# Detailed_Block_Diagram.net
KiCad netlist of a schematic drawn in EAGLE
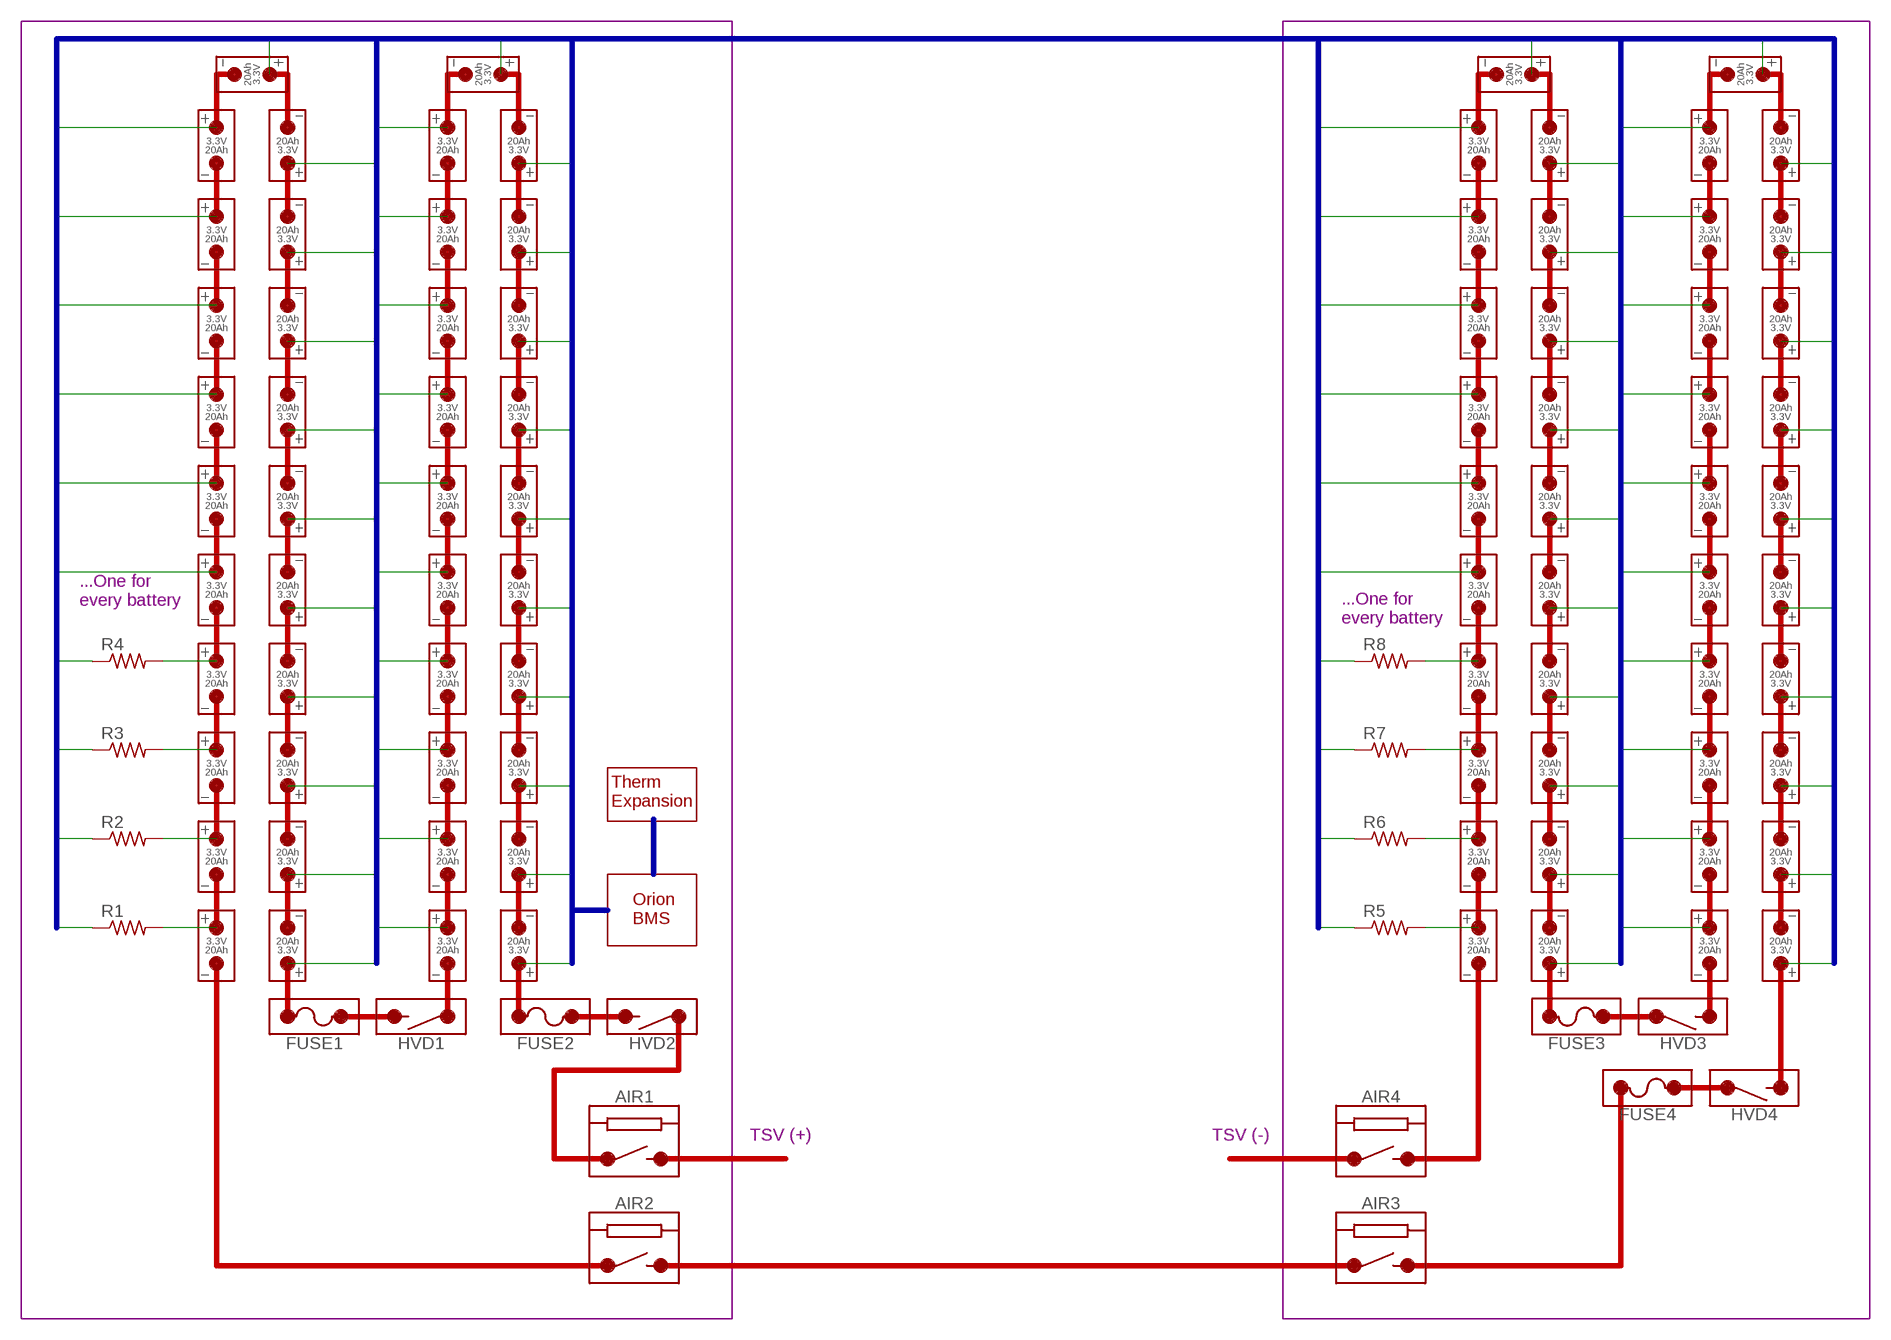
[diagram p0: schematic, sheet 1]

(export (version "E")
  (design (tool "Eeschema 10.0.6"))
  (components
    (comp (ref "AIR1")
      (value "AIR")
      (footprint "eagle-import:AIR")
      (libsource (lib "eagle-import") (part "AIR"))
    )
    (comp (ref "AIR2")
      (value "AIR")
      (footprint "eagle-import:AIR")
      (libsource (lib "eagle-import") (part "AIR"))
    )
    (comp (ref "AIR3")
      (value "AIR")
      (footprint "eagle-import:AIR")
      (libsource (lib "eagle-import") (part "AIR"))
    )
    (comp (ref "AIR4")
      (value "AIR")
      (footprint "eagle-import:AIR")
      (libsource (lib "eagle-import") (part "AIR"))
    )
    (comp (ref "FUSE1")
      (value "FUSE")
      (footprint "eagle-import:FUSE")
      (libsource (lib "eagle-import") (part "FUSE"))
    )
    (comp (ref "FUSE2")
      (value "FUSE")
      (footprint "eagle-import:FUSE")
      (libsource (lib "eagle-import") (part "FUSE"))
    )
    (comp (ref "FUSE3")
      (value "FUSE")
      (footprint "eagle-import:FUSE")
      (libsource (lib "eagle-import") (part "FUSE"))
    )
    (comp (ref "FUSE4")
      (value "FUSE")
      (footprint "eagle-import:FUSE")
      (libsource (lib "eagle-import") (part "FUSE"))
    )
    (comp (ref "HVD1")
      (value "HVD")
      (footprint "eagle-import:HVD")
      (libsource (lib "eagle-import") (part "HVD"))
    )
    (comp (ref "HVD2")
      (value "HVD")
      (footprint "eagle-import:HVD")
      (libsource (lib "eagle-import") (part "HVD"))
    )
    (comp (ref "HVD3")
      (value "HVD")
      (footprint "eagle-import:HVD")
      (libsource (lib "eagle-import") (part "HVD"))
    )
    (comp (ref "HVD4")
      (value "HVD")
      (footprint "eagle-import:HVD")
      (libsource (lib "eagle-import") (part "HVD"))
    )
    (comp (ref "R1")
      (value "R-US_0817/22")
      (footprint "eagle-import:P0817_22")
      (libsource (lib "eagle-import") (part "R-US_0817/22"))
    )
    (comp (ref "R2")
      (value "R-US_0817/22")
      (footprint "eagle-import:P0817_22")
      (libsource (lib "eagle-import") (part "R-US_0817/22"))
    )
    (comp (ref "R3")
      (value "R-US_0817/22")
      (footprint "eagle-import:P0817_22")
      (libsource (lib "eagle-import") (part "R-US_0817/22"))
    )
    (comp (ref "R4")
      (value "R-US_0817/22")
      (footprint "eagle-import:P0817_22")
      (libsource (lib "eagle-import") (part "R-US_0817/22"))
    )
    (comp (ref "R5")
      (value "R-US_0817/22")
      (footprint "eagle-import:P0817_22")
      (libsource (lib "eagle-import") (part "R-US_0817/22"))
    )
    (comp (ref "R6")
      (value "R-US_0817/22")
      (footprint "eagle-import:P0817_22")
      (libsource (lib "eagle-import") (part "R-US_0817/22"))
    )
    (comp (ref "R7")
      (value "R-US_0817/22")
      (footprint "eagle-import:P0817_22")
      (libsource (lib "eagle-import") (part "R-US_0817/22"))
    )
    (comp (ref "R8")
      (value "R-US_0817/22")
      (footprint "eagle-import:P0817_22")
      (libsource (lib "eagle-import") (part "R-US_0817/22"))
    )
    (comp (ref "U$1")
      (value "BAT_CELL")
      (footprint "eagle-import:BAT_CELL")
      (libsource (lib "eagle-import") (part "BAT_CELL"))
    )
    (comp (ref "U$2")
      (value "BAT_CELL")
      (footprint "eagle-import:BAT_CELL")
      (libsource (lib "eagle-import") (part "BAT_CELL"))
    )
    (comp (ref "U$3")
      (value "BAT_CELL")
      (footprint "eagle-import:BAT_CELL")
      (libsource (lib "eagle-import") (part "BAT_CELL"))
    )
    (comp (ref "U$4")
      (value "BAT_CELL")
      (footprint "eagle-import:BAT_CELL")
      (libsource (lib "eagle-import") (part "BAT_CELL"))
    )
    (comp (ref "U$5")
      (value "BAT_CELL")
      (footprint "eagle-import:BAT_CELL")
      (libsource (lib "eagle-import") (part "BAT_CELL"))
    )
    (comp (ref "U$6")
      (value "BAT_CELL")
      (footprint "eagle-import:BAT_CELL")
      (libsource (lib "eagle-import") (part "BAT_CELL"))
    )
    (comp (ref "U$7")
      (value "BAT_CELL")
      (footprint "eagle-import:BAT_CELL")
      (libsource (lib "eagle-import") (part "BAT_CELL"))
    )
    (comp (ref "U$8")
      (value "BAT_CELL")
      (footprint "eagle-import:BAT_CELL")
      (libsource (lib "eagle-import") (part "BAT_CELL"))
    )
    (comp (ref "U$9")
      (value "BAT_CELL")
      (footprint "eagle-import:BAT_CELL")
      (libsource (lib "eagle-import") (part "BAT_CELL"))
    )
    (comp (ref "U$10")
      (value "BAT_CELL")
      (footprint "eagle-import:BAT_CELL")
      (libsource (lib "eagle-import") (part "BAT_CELL"))
    )
    (comp (ref "U$11")
      (value "BAT_CELL")
      (footprint "eagle-import:BAT_CELL")
      (libsource (lib "eagle-import") (part "BAT_CELL"))
    )
    (comp (ref "U$12")
      (value "BAT_CELL")
      (footprint "eagle-import:BAT_CELL")
      (libsource (lib "eagle-import") (part "BAT_CELL"))
    )
    (comp (ref "U$13")
      (value "BAT_CELL")
      (footprint "eagle-import:BAT_CELL")
      (libsource (lib "eagle-import") (part "BAT_CELL"))
    )
    (comp (ref "U$14")
      (value "BAT_CELL")
      (footprint "eagle-import:BAT_CELL")
      (libsource (lib "eagle-import") (part "BAT_CELL"))
    )
    (comp (ref "U$15")
      (value "BAT_CELL")
      (footprint "eagle-import:BAT_CELL")
      (libsource (lib "eagle-import") (part "BAT_CELL"))
    )
    (comp (ref "U$16")
      (value "BAT_CELL")
      (footprint "eagle-import:BAT_CELL")
      (libsource (lib "eagle-import") (part "BAT_CELL"))
    )
    (comp (ref "U$17")
      (value "BAT_CELL")
      (footprint "eagle-import:BAT_CELL")
      (libsource (lib "eagle-import") (part "BAT_CELL"))
    )
    (comp (ref "U$18")
      (value "BAT_CELL")
      (footprint "eagle-import:BAT_CELL")
      (libsource (lib "eagle-import") (part "BAT_CELL"))
    )
    (comp (ref "U$19")
      (value "BAT_CELL")
      (footprint "eagle-import:BAT_CELL")
      (libsource (lib "eagle-import") (part "BAT_CELL"))
    )
    (comp (ref "U$20")
      (value "BAT_CELL")
      (footprint "eagle-import:BAT_CELL")
      (libsource (lib "eagle-import") (part "BAT_CELL"))
    )
    (comp (ref "U$21")
      (value "BAT_CELL")
      (footprint "eagle-import:BAT_CELL")
      (libsource (lib "eagle-import") (part "BAT_CELL"))
    )
    (comp (ref "U$22")
      (value "BAT_CELL")
      (footprint "eagle-import:BAT_CELL")
      (libsource (lib "eagle-import") (part "BAT_CELL"))
    )
    (comp (ref "U$23")
      (value "BAT_CELL")
      (footprint "eagle-import:BAT_CELL")
      (libsource (lib "eagle-import") (part "BAT_CELL"))
    )
    (comp (ref "U$24")
      (value "BAT_CELL")
      (footprint "eagle-import:BAT_CELL")
      (libsource (lib "eagle-import") (part "BAT_CELL"))
    )
    (comp (ref "U$25")
      (value "BAT_CELL")
      (footprint "eagle-import:BAT_CELL")
      (libsource (lib "eagle-import") (part "BAT_CELL"))
    )
    (comp (ref "U$26")
      (value "BAT_CELL")
      (footprint "eagle-import:BAT_CELL")
      (libsource (lib "eagle-import") (part "BAT_CELL"))
    )
    (comp (ref "U$27")
      (value "BAT_CELL")
      (footprint "eagle-import:BAT_CELL")
      (libsource (lib "eagle-import") (part "BAT_CELL"))
    )
    (comp (ref "U$28")
      (value "BAT_CELL")
      (footprint "eagle-import:BAT_CELL")
      (libsource (lib "eagle-import") (part "BAT_CELL"))
    )
    (comp (ref "U$29")
      (value "BAT_CELL")
      (footprint "eagle-import:BAT_CELL")
      (libsource (lib "eagle-import") (part "BAT_CELL"))
    )
    (comp (ref "U$30")
      (value "BAT_CELL")
      (footprint "eagle-import:BAT_CELL")
      (libsource (lib "eagle-import") (part "BAT_CELL"))
    )
    (comp (ref "U$31")
      (value "BAT_CELL")
      (footprint "eagle-import:BAT_CELL")
      (libsource (lib "eagle-import") (part "BAT_CELL"))
    )
    (comp (ref "U$32")
      (value "BAT_CELL")
      (footprint "eagle-import:BAT_CELL")
      (libsource (lib "eagle-import") (part "BAT_CELL"))
    )
    (comp (ref "U$33")
      (value "BAT_CELL")
      (footprint "eagle-import:BAT_CELL")
      (libsource (lib "eagle-import") (part "BAT_CELL"))
    )
    (comp (ref "U$34")
      (value "BAT_CELL")
      (footprint "eagle-import:BAT_CELL")
      (libsource (lib "eagle-import") (part "BAT_CELL"))
    )
    (comp (ref "U$35")
      (value "BAT_CELL")
      (footprint "eagle-import:BAT_CELL")
      (libsource (lib "eagle-import") (part "BAT_CELL"))
    )
    (comp (ref "U$36")
      (value "BAT_CELL")
      (footprint "eagle-import:BAT_CELL")
      (libsource (lib "eagle-import") (part "BAT_CELL"))
    )
    (comp (ref "U$37")
      (value "BAT_CELL")
      (footprint "eagle-import:BAT_CELL")
      (libsource (lib "eagle-import") (part "BAT_CELL"))
    )
    (comp (ref "U$38")
      (value "BAT_CELL")
      (footprint "eagle-import:BAT_CELL")
      (libsource (lib "eagle-import") (part "BAT_CELL"))
    )
    (comp (ref "U$39")
      (value "BAT_CELL")
      (footprint "eagle-import:BAT_CELL")
      (libsource (lib "eagle-import") (part "BAT_CELL"))
    )
    (comp (ref "U$40")
      (value "BAT_CELL")
      (footprint "eagle-import:BAT_CELL")
      (libsource (lib "eagle-import") (part "BAT_CELL"))
    )
    (comp (ref "U$41")
      (value "BAT_CELL")
      (footprint "eagle-import:BAT_CELL")
      (libsource (lib "eagle-import") (part "BAT_CELL"))
    )
    (comp (ref "U$42")
      (value "BAT_CELL")
      (footprint "eagle-import:BAT_CELL")
      (libsource (lib "eagle-import") (part "BAT_CELL"))
    )
    (comp (ref "U$43")
      (value "BAT_CELL")
      (footprint "eagle-import:BAT_CELL")
      (libsource (lib "eagle-import") (part "BAT_CELL"))
    )
    (comp (ref "U$44")
      (value "BAT_CELL")
      (footprint "eagle-import:BAT_CELL")
      (libsource (lib "eagle-import") (part "BAT_CELL"))
    )
    (comp (ref "U$45")
      (value "BAT_CELL")
      (footprint "eagle-import:BAT_CELL")
      (libsource (lib "eagle-import") (part "BAT_CELL"))
    )
    (comp (ref "U$46")
      (value "BAT_CELL")
      (footprint "eagle-import:BAT_CELL")
      (libsource (lib "eagle-import") (part "BAT_CELL"))
    )
    (comp (ref "U$47")
      (value "BAT_CELL")
      (footprint "eagle-import:BAT_CELL")
      (libsource (lib "eagle-import") (part "BAT_CELL"))
    )
    (comp (ref "U$48")
      (value "BAT_CELL")
      (footprint "eagle-import:BAT_CELL")
      (libsource (lib "eagle-import") (part "BAT_CELL"))
    )
    (comp (ref "U$49")
      (value "BAT_CELL")
      (footprint "eagle-import:BAT_CELL")
      (libsource (lib "eagle-import") (part "BAT_CELL"))
    )
    (comp (ref "U$50")
      (value "BAT_CELL")
      (footprint "eagle-import:BAT_CELL")
      (libsource (lib "eagle-import") (part "BAT_CELL"))
    )
    (comp (ref "U$51")
      (value "BAT_CELL")
      (footprint "eagle-import:BAT_CELL")
      (libsource (lib "eagle-import") (part "BAT_CELL"))
    )
    (comp (ref "U$52")
      (value "BAT_CELL")
      (footprint "eagle-import:BAT_CELL")
      (libsource (lib "eagle-import") (part "BAT_CELL"))
    )
    (comp (ref "U$53")
      (value "BAT_CELL")
      (footprint "eagle-import:BAT_CELL")
      (libsource (lib "eagle-import") (part "BAT_CELL"))
    )
    (comp (ref "U$54")
      (value "BAT_CELL")
      (footprint "eagle-import:BAT_CELL")
      (libsource (lib "eagle-import") (part "BAT_CELL"))
    )
    (comp (ref "U$55")
      (value "BAT_CELL")
      (footprint "eagle-import:BAT_CELL")
      (libsource (lib "eagle-import") (part "BAT_CELL"))
    )
    (comp (ref "U$56")
      (value "BAT_CELL")
      (footprint "eagle-import:BAT_CELL")
      (libsource (lib "eagle-import") (part "BAT_CELL"))
    )
    (comp (ref "U$57")
      (value "BAT_CELL")
      (footprint "eagle-import:BAT_CELL")
      (libsource (lib "eagle-import") (part "BAT_CELL"))
    )
    (comp (ref "U$58")
      (value "BAT_CELL")
      (footprint "eagle-import:BAT_CELL")
      (libsource (lib "eagle-import") (part "BAT_CELL"))
    )
    (comp (ref "U$59")
      (value "BAT_CELL")
      (footprint "eagle-import:BAT_CELL")
      (libsource (lib "eagle-import") (part "BAT_CELL"))
    )
    (comp (ref "U$60")
      (value "BAT_CELL")
      (footprint "eagle-import:BAT_CELL")
      (libsource (lib "eagle-import") (part "BAT_CELL"))
    )
    (comp (ref "U$61")
      (value "BAT_CELL")
      (footprint "eagle-import:BAT_CELL")
      (libsource (lib "eagle-import") (part "BAT_CELL"))
    )
    (comp (ref "U$62")
      (value "BAT_CELL")
      (footprint "eagle-import:BAT_CELL")
      (libsource (lib "eagle-import") (part "BAT_CELL"))
    )
    (comp (ref "U$63")
      (value "BAT_CELL")
      (footprint "eagle-import:BAT_CELL")
      (libsource (lib "eagle-import") (part "BAT_CELL"))
    )
    (comp (ref "U$64")
      (value "BAT_CELL")
      (footprint "eagle-import:BAT_CELL")
      (libsource (lib "eagle-import") (part "BAT_CELL"))
    )
    (comp (ref "U$65")
      (value "BAT_CELL")
      (footprint "eagle-import:BAT_CELL")
      (libsource (lib "eagle-import") (part "BAT_CELL"))
    )
    (comp (ref "U$66")
      (value "BAT_CELL")
      (footprint "eagle-import:BAT_CELL")
      (libsource (lib "eagle-import") (part "BAT_CELL"))
    )
    (comp (ref "U$67")
      (value "BAT_CELL")
      (footprint "eagle-import:BAT_CELL")
      (libsource (lib "eagle-import") (part "BAT_CELL"))
    )
    (comp (ref "U$68")
      (value "BAT_CELL")
      (footprint "eagle-import:BAT_CELL")
      (libsource (lib "eagle-import") (part "BAT_CELL"))
    )
    (comp (ref "U$69")
      (value "BAT_CELL")
      (footprint "eagle-import:BAT_CELL")
      (libsource (lib "eagle-import") (part "BAT_CELL"))
    )
    (comp (ref "U$70")
      (value "BAT_CELL")
      (footprint "eagle-import:BAT_CELL")
      (libsource (lib "eagle-import") (part "BAT_CELL"))
    )
    (comp (ref "U$71")
      (value "BAT_CELL")
      (footprint "eagle-import:BAT_CELL")
      (libsource (lib "eagle-import") (part "BAT_CELL"))
    )
    (comp (ref "U$72")
      (value "BAT_CELL")
      (footprint "eagle-import:BAT_CELL")
      (libsource (lib "eagle-import") (part "BAT_CELL"))
    )
    (comp (ref "U$73")
      (value "BAT_CELL")
      (footprint "eagle-import:BAT_CELL")
      (libsource (lib "eagle-import") (part "BAT_CELL"))
    )
    (comp (ref "U$74")
      (value "BAT_CELL")
      (footprint "eagle-import:BAT_CELL")
      (libsource (lib "eagle-import") (part "BAT_CELL"))
    )
    (comp (ref "U$75")
      (value "BAT_CELL")
      (footprint "eagle-import:BAT_CELL")
      (libsource (lib "eagle-import") (part "BAT_CELL"))
    )
    (comp (ref "U$76")
      (value "BAT_CELL")
      (footprint "eagle-import:BAT_CELL")
      (libsource (lib "eagle-import") (part "BAT_CELL"))
    )
    (comp (ref "U$77")
      (value "BAT_CELL")
      (footprint "eagle-import:BAT_CELL")
      (libsource (lib "eagle-import") (part "BAT_CELL"))
    )
    (comp (ref "U$78")
      (value "BAT_CELL")
      (footprint "eagle-import:BAT_CELL")
      (libsource (lib "eagle-import") (part "BAT_CELL"))
    )
    (comp (ref "U$79")
      (value "BAT_CELL")
      (footprint "eagle-import:BAT_CELL")
      (libsource (lib "eagle-import") (part "BAT_CELL"))
    )
    (comp (ref "U$80")
      (value "BAT_CELL")
      (footprint "eagle-import:BAT_CELL")
      (libsource (lib "eagle-import") (part "BAT_CELL"))
    )
    (comp (ref "U$81")
      (value "BAT_CELL")
      (footprint "eagle-import:BAT_CELL")
      (libsource (lib "eagle-import") (part "BAT_CELL"))
    )
    (comp (ref "U$82")
      (value "BAT_CELL")
      (footprint "eagle-import:BAT_CELL")
      (libsource (lib "eagle-import") (part "BAT_CELL"))
    )
    (comp (ref "U$83")
      (value "BAT_CELL")
      (footprint "eagle-import:BAT_CELL")
      (libsource (lib "eagle-import") (part "BAT_CELL"))
    )
    (comp (ref "U$84")
      (value "BAT_CELL")
      (footprint "eagle-import:BAT_CELL")
      (libsource (lib "eagle-import") (part "BAT_CELL"))
    )
  )
  (nets
    (net (code "1") (name "/B$1") (class "Default")
      (node (ref "R1") (pin "1") (pinfunction "1_1") (pintype "passive"))
      (node (ref "R2") (pin "1") (pinfunction "1_1") (pintype "passive"))
      (node (ref "R3") (pin "1") (pinfunction "1_1") (pintype "passive"))
      (node (ref "R4") (pin "1") (pinfunction "1_1") (pintype "passive"))
      (node (ref "R5") (pin "1") (pinfunction "1_1") (pintype "passive"))
      (node (ref "R6") (pin "1") (pinfunction "1_1") (pintype "passive"))
      (node (ref "R7") (pin "1") (pinfunction "1_1") (pintype "passive"))
      (node (ref "R8") (pin "1") (pinfunction "1_1") (pintype "passive"))
      (node (ref "U$1") (pin "+") (pinfunction "+_+") (pintype "bidirectional"))
      (node (ref "U$10") (pin "+") (pinfunction "+_+") (pintype "bidirectional"))
      (node (ref "U$11") (pin "+") (pinfunction "+_+") (pintype "bidirectional"))
      (node (ref "U$12") (pin "+") (pinfunction "+_+") (pintype "bidirectional"))
      (node (ref "U$13") (pin "+") (pinfunction "+_+") (pintype "bidirectional"))
      (node (ref "U$14") (pin "+") (pinfunction "+_+") (pintype "bidirectional"))
      (node (ref "U$15") (pin "+") (pinfunction "+_+") (pintype "bidirectional"))
      (node (ref "U$16") (pin "+") (pinfunction "+_+") (pintype "bidirectional"))
      (node (ref "U$17") (pin "+") (pinfunction "+_+") (pintype "bidirectional"))
      (node (ref "U$18") (pin "+") (pinfunction "+_+") (pintype "bidirectional"))
      (node (ref "U$19") (pin "+") (pinfunction "+_+") (pintype "bidirectional"))
      (node (ref "U$2") (pin "+") (pinfunction "+_+") (pintype "bidirectional"))
      (node (ref "U$20") (pin "+") (pinfunction "+_+") (pintype "bidirectional"))
      (node (ref "U$21") (pin "+") (pinfunction "+_+") (pintype "bidirectional"))
      (node (ref "U$22") (pin "+") (pinfunction "+_+") (pintype "bidirectional"))
      (node (ref "U$23") (pin "+") (pinfunction "+_+") (pintype "bidirectional"))
      (node (ref "U$24") (pin "+") (pinfunction "+_+") (pintype "bidirectional"))
      (node (ref "U$25") (pin "+") (pinfunction "+_+") (pintype "bidirectional"))
      (node (ref "U$26") (pin "+") (pinfunction "+_+") (pintype "bidirectional"))
      (node (ref "U$27") (pin "+") (pinfunction "+_+") (pintype "bidirectional"))
      (node (ref "U$28") (pin "+") (pinfunction "+_+") (pintype "bidirectional"))
      (node (ref "U$29") (pin "+") (pinfunction "+_+") (pintype "bidirectional"))
      (node (ref "U$3") (pin "+") (pinfunction "+_+") (pintype "bidirectional"))
      (node (ref "U$30") (pin "+") (pinfunction "+_+") (pintype "bidirectional"))
      (node (ref "U$31") (pin "+") (pinfunction "+_+") (pintype "bidirectional"))
      (node (ref "U$32") (pin "+") (pinfunction "+_+") (pintype "bidirectional"))
      (node (ref "U$33") (pin "+") (pinfunction "+_+") (pintype "bidirectional"))
      (node (ref "U$34") (pin "+") (pinfunction "+_+") (pintype "bidirectional"))
      (node (ref "U$35") (pin "+") (pinfunction "+_+") (pintype "bidirectional"))
      (node (ref "U$36") (pin "+") (pinfunction "+_+") (pintype "bidirectional"))
      (node (ref "U$37") (pin "+") (pinfunction "+_+") (pintype "bidirectional"))
      (node (ref "U$38") (pin "+") (pinfunction "+_+") (pintype "bidirectional"))
      (node (ref "U$39") (pin "+") (pinfunction "+_+") (pintype "bidirectional"))
      (node (ref "U$4") (pin "+") (pinfunction "+_+") (pintype "bidirectional"))
      (node (ref "U$40") (pin "+") (pinfunction "+_+") (pintype "bidirectional"))
      (node (ref "U$41") (pin "+") (pinfunction "+_+") (pintype "bidirectional"))
      (node (ref "U$42") (pin "+") (pinfunction "+_+") (pintype "bidirectional"))
      (node (ref "U$43") (pin "+") (pinfunction "+_+") (pintype "bidirectional"))
      (node (ref "U$44") (pin "+") (pinfunction "+_+") (pintype "bidirectional"))
      (node (ref "U$45") (pin "+") (pinfunction "+_+") (pintype "bidirectional"))
      (node (ref "U$46") (pin "+") (pinfunction "+_+") (pintype "bidirectional"))
      (node (ref "U$47") (pin "+") (pinfunction "+_+") (pintype "bidirectional"))
      (node (ref "U$48") (pin "+") (pinfunction "+_+") (pintype "bidirectional"))
      (node (ref "U$49") (pin "+") (pinfunction "+_+") (pintype "bidirectional"))
      (node (ref "U$5") (pin "+") (pinfunction "+_+") (pintype "bidirectional"))
      (node (ref "U$50") (pin "+") (pinfunction "+_+") (pintype "bidirectional"))
      (node (ref "U$51") (pin "+") (pinfunction "+_+") (pintype "bidirectional"))
      (node (ref "U$52") (pin "+") (pinfunction "+_+") (pintype "bidirectional"))
      (node (ref "U$53") (pin "+") (pinfunction "+_+") (pintype "bidirectional"))
      (node (ref "U$54") (pin "+") (pinfunction "+_+") (pintype "bidirectional"))
      (node (ref "U$55") (pin "+") (pinfunction "+_+") (pintype "bidirectional"))
      (node (ref "U$56") (pin "+") (pinfunction "+_+") (pintype "bidirectional"))
      (node (ref "U$57") (pin "+") (pinfunction "+_+") (pintype "bidirectional"))
      (node (ref "U$58") (pin "+") (pinfunction "+_+") (pintype "bidirectional"))
      (node (ref "U$59") (pin "+") (pinfunction "+_+") (pintype "bidirectional"))
      (node (ref "U$60") (pin "+") (pinfunction "+_+") (pintype "bidirectional"))
      (node (ref "U$61") (pin "+") (pinfunction "+_+") (pintype "bidirectional"))
      (node (ref "U$62") (pin "+") (pinfunction "+_+") (pintype "bidirectional"))
      (node (ref "U$63") (pin "+") (pinfunction "+_+") (pintype "bidirectional"))
      (node (ref "U$64") (pin "+") (pinfunction "+_+") (pintype "bidirectional"))
      (node (ref "U$65") (pin "+") (pinfunction "+_+") (pintype "bidirectional"))
      (node (ref "U$66") (pin "+") (pinfunction "+_+") (pintype "bidirectional"))
      (node (ref "U$67") (pin "+") (pinfunction "+_+") (pintype "bidirectional"))
      (node (ref "U$68") (pin "+") (pinfunction "+_+") (pintype "bidirectional"))
      (node (ref "U$73") (pin "+") (pinfunction "+_+") (pintype "bidirectional"))
      (node (ref "U$74") (pin "+") (pinfunction "+_+") (pintype "bidirectional"))
      (node (ref "U$75") (pin "+") (pinfunction "+_+") (pintype "bidirectional"))
      (node (ref "U$76") (pin "+") (pinfunction "+_+") (pintype "bidirectional"))
      (node (ref "U$77") (pin "+") (pinfunction "+_+") (pintype "bidirectional"))
      (node (ref "U$78") (pin "+") (pinfunction "+_+") (pintype "bidirectional"))
      (node (ref "U$79") (pin "+") (pinfunction "+_+") (pintype "bidirectional"))
      (node (ref "U$80") (pin "+") (pinfunction "+_+") (pintype "bidirectional"))
      (node (ref "U$81") (pin "+") (pinfunction "+_+") (pintype "bidirectional"))
      (node (ref "U$82") (pin "+") (pinfunction "+_+") (pintype "bidirectional"))
      (node (ref "U$83") (pin "+") (pinfunction "+_+") (pintype "bidirectional"))
      (node (ref "U$84") (pin "+") (pinfunction "+_+") (pintype "bidirectional"))
    )
    (net (code "2") (name "Net-(R1-Pad2)") (class "Default")
      (node (ref "R1") (pin "2") (pinfunction "2_2") (pintype "passive"))
      (node (ref "U$9") (pin "+") (pinfunction "+_+") (pintype "bidirectional"))
    )
    (net (code "3") (name "Net-(R2-Pad2)") (class "Default")
      (node (ref "R2") (pin "2") (pinfunction "2_2") (pintype "passive"))
      (node (ref "U$8") (pin "+") (pinfunction "+_+") (pintype "bidirectional"))
    )
    (net (code "4") (name "Net-(R3-Pad2)") (class "Default")
      (node (ref "R3") (pin "2") (pinfunction "2_2") (pintype "passive"))
      (node (ref "U$7") (pin "+") (pinfunction "+_+") (pintype "bidirectional"))
    )
    (net (code "5") (name "Net-(R4-Pad2)") (class "Default")
      (node (ref "R4") (pin "2") (pinfunction "2_2") (pintype "passive"))
      (node (ref "U$6") (pin "+") (pinfunction "+_+") (pintype "bidirectional"))
    )
    (net (code "6") (name "Net-(R5-Pad2)") (class "Default")
      (node (ref "R5") (pin "2") (pinfunction "2_2") (pintype "passive"))
      (node (ref "U$72") (pin "+") (pinfunction "+_+") (pintype "bidirectional"))
    )
    (net (code "7") (name "Net-(R6-Pad2)") (class "Default")
      (node (ref "R6") (pin "2") (pinfunction "2_2") (pintype "passive"))
      (node (ref "U$71") (pin "+") (pinfunction "+_+") (pintype "bidirectional"))
    )
    (net (code "8") (name "Net-(R7-Pad2)") (class "Default")
      (node (ref "R7") (pin "2") (pinfunction "2_2") (pintype "passive"))
      (node (ref "U$70") (pin "+") (pinfunction "+_+") (pintype "bidirectional"))
    )
    (net (code "9") (name "Net-(R8-Pad2)") (class "Default")
      (node (ref "R8") (pin "2") (pinfunction "2_2") (pintype "passive"))
      (node (ref "U$69") (pin "+") (pinfunction "+_+") (pintype "bidirectional"))
    )
    (net (code "10") (name "unconnected-(AIR1-1-PadP$1)") (class "Default")
      (node (ref "AIR1") (pin "P$1") (pinfunction "1_P$1") (pintype "passive"))
    )
    (net (code "11") (name "unconnected-(AIR1-2-PadP$2)") (class "Default")
      (node (ref "AIR1") (pin "P$2") (pinfunction "2_P$2") (pintype "passive"))
    )
    (net (code "12") (name "unconnected-(AIR1-P$1-PadP$3)") (class "Default")
      (node (ref "AIR1") (pin "P$3") (pinfunction "P$1_P$3") (pintype "bidirectional"))
    )
    (net (code "13") (name "unconnected-(AIR1-P$2-PadP$4)") (class "Default")
      (node (ref "AIR1") (pin "P$4") (pinfunction "P$2_P$4") (pintype "bidirectional"))
    )
    (net (code "14") (name "unconnected-(AIR2-1-PadP$1)") (class "Default")
      (node (ref "AIR2") (pin "P$1") (pinfunction "1_P$1") (pintype "passive"))
    )
    (net (code "15") (name "unconnected-(AIR2-2-PadP$2)") (class "Default")
      (node (ref "AIR2") (pin "P$2") (pinfunction "2_P$2") (pintype "passive"))
    )
    (net (code "16") (name "unconnected-(AIR2-P$1-PadP$3)") (class "Default")
      (node (ref "AIR2") (pin "P$3") (pinfunction "P$1_P$3") (pintype "bidirectional"))
    )
    (net (code "17") (name "unconnected-(AIR2-P$2-PadP$4)") (class "Default")
      (node (ref "AIR2") (pin "P$4") (pinfunction "P$2_P$4") (pintype "bidirectional"))
    )
    (net (code "18") (name "unconnected-(AIR3-1-PadP$1)") (class "Default")
      (node (ref "AIR3") (pin "P$1") (pinfunction "1_P$1") (pintype "passive"))
    )
    (net (code "19") (name "unconnected-(AIR3-2-PadP$2)") (class "Default")
      (node (ref "AIR3") (pin "P$2") (pinfunction "2_P$2") (pintype "passive"))
    )
    (net (code "20") (name "unconnected-(AIR3-P$1-PadP$3)") (class "Default")
      (node (ref "AIR3") (pin "P$3") (pinfunction "P$1_P$3") (pintype "bidirectional"))
    )
    (net (code "21") (name "unconnected-(AIR3-P$2-PadP$4)") (class "Default")
      (node (ref "AIR3") (pin "P$4") (pinfunction "P$2_P$4") (pintype "bidirectional"))
    )
    (net (code "22") (name "unconnected-(AIR4-1-PadP$1)") (class "Default")
      (node (ref "AIR4") (pin "P$1") (pinfunction "1_P$1") (pintype "passive"))
    )
    (net (code "23") (name "unconnected-(AIR4-2-PadP$2)") (class "Default")
      (node (ref "AIR4") (pin "P$2") (pinfunction "2_P$2") (pintype "passive"))
    )
    (net (code "24") (name "unconnected-(AIR4-P$1-PadP$3)") (class "Default")
      (node (ref "AIR4") (pin "P$3") (pinfunction "P$1_P$3") (pintype "bidirectional"))
    )
    (net (code "25") (name "unconnected-(AIR4-P$2-PadP$4)") (class "Default")
      (node (ref "AIR4") (pin "P$4") (pinfunction "P$2_P$4") (pintype "bidirectional"))
    )
    (net (code "26") (name "unconnected-(FUSE1-Pad1)") (class "Default")
      (node (ref "FUSE1") (pin "1") (pinfunction "1_1") (pintype "passive"))
    )
    (net (code "27") (name "unconnected-(FUSE1-Pad2)") (class "Default")
      (node (ref "FUSE1") (pin "2") (pinfunction "2_2") (pintype "passive"))
    )
    (net (code "28") (name "unconnected-(FUSE2-Pad1)") (class "Default")
      (node (ref "FUSE2") (pin "1") (pinfunction "1_1") (pintype "passive"))
    )
    (net (code "29") (name "unconnected-(FUSE2-Pad2)") (class "Default")
      (node (ref "FUSE2") (pin "2") (pinfunction "2_2") (pintype "passive"))
    )
    (net (code "30") (name "unconnected-(FUSE3-Pad1)") (class "Default")
      (node (ref "FUSE3") (pin "1") (pinfunction "1_1") (pintype "passive"))
    )
    (net (code "31") (name "unconnected-(FUSE3-Pad2)") (class "Default")
      (node (ref "FUSE3") (pin "2") (pinfunction "2_2") (pintype "passive"))
    )
    (net (code "32") (name "unconnected-(FUSE4-Pad1)") (class "Default")
      (node (ref "FUSE4") (pin "1") (pinfunction "1_1") (pintype "passive"))
    )
    (net (code "33") (name "unconnected-(FUSE4-Pad2)") (class "Default")
      (node (ref "FUSE4") (pin "2") (pinfunction "2_2") (pintype "passive"))
    )
    (net (code "34") (name "unconnected-(HVD1-1-PadP$1)") (class "Default")
      (node (ref "HVD1") (pin "P$1") (pinfunction "1_P$1") (pintype "passive"))
    )
    (net (code "35") (name "unconnected-(HVD1-2-PadP$2)") (class "Default")
      (node (ref "HVD1") (pin "P$2") (pinfunction "2_P$2") (pintype "passive"))
    )
    (net (code "36") (name "unconnected-(HVD2-1-PadP$1)") (class "Default")
      (node (ref "HVD2") (pin "P$1") (pinfunction "1_P$1") (pintype "passive"))
    )
    (net (code "37") (name "unconnected-(HVD2-2-PadP$2)") (class "Default")
      (node (ref "HVD2") (pin "P$2") (pinfunction "2_P$2") (pintype "passive"))
    )
    (net (code "38") (name "unconnected-(HVD3-1-PadP$1)") (class "Default")
      (node (ref "HVD3") (pin "P$1") (pinfunction "1_P$1") (pintype "passive"))
    )
    (net (code "39") (name "unconnected-(HVD3-2-PadP$2)") (class "Default")
      (node (ref "HVD3") (pin "P$2") (pinfunction "2_P$2") (pintype "passive"))
    )
    (net (code "40") (name "unconnected-(HVD4-1-PadP$1)") (class "Default")
      (node (ref "HVD4") (pin "P$1") (pinfunction "1_P$1") (pintype "passive"))
    )
    (net (code "41") (name "unconnected-(HVD4-2-PadP$2)") (class "Default")
      (node (ref "HVD4") (pin "P$2") (pinfunction "2_P$2") (pintype "passive"))
    )
    (net (code "42") (name "unconnected-(U$1-Pad-)") (class "Default")
      (node (ref "U$1") (pin "-") (pinfunction "-_-") (pintype "bidirectional"))
    )
    (net (code "43") (name "unconnected-(U$2-Pad-)") (class "Default")
      (node (ref "U$2") (pin "-") (pinfunction "-_-") (pintype "bidirectional"))
    )
    (net (code "44") (name "unconnected-(U$3-Pad-)") (class "Default")
      (node (ref "U$3") (pin "-") (pinfunction "-_-") (pintype "bidirectional"))
    )
    (net (code "45") (name "unconnected-(U$4-Pad-)") (class "Default")
      (node (ref "U$4") (pin "-") (pinfunction "-_-") (pintype "bidirectional"))
    )
    (net (code "46") (name "unconnected-(U$5-Pad-)") (class "Default")
      (node (ref "U$5") (pin "-") (pinfunction "-_-") (pintype "bidirectional"))
    )
    (net (code "47") (name "unconnected-(U$6-Pad-)") (class "Default")
      (node (ref "U$6") (pin "-") (pinfunction "-_-") (pintype "bidirectional"))
    )
    (net (code "48") (name "unconnected-(U$7-Pad-)") (class "Default")
      (node (ref "U$7") (pin "-") (pinfunction "-_-") (pintype "bidirectional"))
    )
    (net (code "49") (name "unconnected-(U$8-Pad-)") (class "Default")
      (node (ref "U$8") (pin "-") (pinfunction "-_-") (pintype "bidirectional"))
    )
    (net (code "50") (name "unconnected-(U$9-Pad-)") (class "Default")
      (node (ref "U$9") (pin "-") (pinfunction "-_-") (pintype "bidirectional"))
    )
    (net (code "51") (name "unconnected-(U$10-Pad-)") (class "Default")
      (node (ref "U$10") (pin "-") (pinfunction "-_-") (pintype "bidirectional"))
    )
    (net (code "52") (name "unconnected-(U$11-Pad-)") (class "Default")
      (node (ref "U$11") (pin "-") (pinfunction "-_-") (pintype "bidirectional"))
    )
    (net (code "53") (name "unconnected-(U$12-Pad-)") (class "Default")
      (node (ref "U$12") (pin "-") (pinfunction "-_-") (pintype "bidirectional"))
    )
    (net (code "54") (name "unconnected-(U$13-Pad-)") (class "Default")
      (node (ref "U$13") (pin "-") (pinfunction "-_-") (pintype "bidirectional"))
    )
    (net (code "55") (name "unconnected-(U$14-Pad-)") (class "Default")
      (node (ref "U$14") (pin "-") (pinfunction "-_-") (pintype "bidirectional"))
    )
    (net (code "56") (name "unconnected-(U$15-Pad-)") (class "Default")
      (node (ref "U$15") (pin "-") (pinfunction "-_-") (pintype "bidirectional"))
    )
    (net (code "57") (name "unconnected-(U$16-Pad-)") (class "Default")
      (node (ref "U$16") (pin "-") (pinfunction "-_-") (pintype "bidirectional"))
    )
    (net (code "58") (name "unconnected-(U$17-Pad-)") (class "Default")
      (node (ref "U$17") (pin "-") (pinfunction "-_-") (pintype "bidirectional"))
    )
    (net (code "59") (name "unconnected-(U$18-Pad-)") (class "Default")
      (node (ref "U$18") (pin "-") (pinfunction "-_-") (pintype "bidirectional"))
    )
    (net (code "60") (name "unconnected-(U$19-Pad-)") (class "Default")
      (node (ref "U$19") (pin "-") (pinfunction "-_-") (pintype "bidirectional"))
    )
    (net (code "61") (name "unconnected-(U$20-Pad-)") (class "Default")
      (node (ref "U$20") (pin "-") (pinfunction "-_-") (pintype "bidirectional"))
    )
    (net (code "62") (name "unconnected-(U$21-Pad-)") (class "Default")
      (node (ref "U$21") (pin "-") (pinfunction "-_-") (pintype "bidirectional"))
    )
    (net (code "63") (name "unconnected-(U$22-Pad-)") (class "Default")
      (node (ref "U$22") (pin "-") (pinfunction "-_-") (pintype "bidirectional"))
    )
    (net (code "64") (name "unconnected-(U$23-Pad-)") (class "Default")
      (node (ref "U$23") (pin "-") (pinfunction "-_-") (pintype "bidirectional"))
    )
    (net (code "65") (name "unconnected-(U$24-Pad-)") (class "Default")
      (node (ref "U$24") (pin "-") (pinfunction "-_-") (pintype "bidirectional"))
    )
    (net (code "66") (name "unconnected-(U$25-Pad-)") (class "Default")
      (node (ref "U$25") (pin "-") (pinfunction "-_-") (pintype "bidirectional"))
    )
    (net (code "67") (name "unconnected-(U$26-Pad-)") (class "Default")
      (node (ref "U$26") (pin "-") (pinfunction "-_-") (pintype "bidirectional"))
    )
    (net (code "68") (name "unconnected-(U$27-Pad-)") (class "Default")
      (node (ref "U$27") (pin "-") (pinfunction "-_-") (pintype "bidirectional"))
    )
    (net (code "69") (name "unconnected-(U$28-Pad-)") (class "Default")
      (node (ref "U$28") (pin "-") (pinfunction "-_-") (pintype "bidirectional"))
    )
    (net (code "70") (name "unconnected-(U$29-Pad-)") (class "Default")
      (node (ref "U$29") (pin "-") (pinfunction "-_-") (pintype "bidirectional"))
    )
    (net (code "71") (name "unconnected-(U$30-Pad-)") (class "Default")
      (node (ref "U$30") (pin "-") (pinfunction "-_-") (pintype "bidirectional"))
    )
    (net (code "72") (name "unconnected-(U$31-Pad-)") (class "Default")
      (node (ref "U$31") (pin "-") (pinfunction "-_-") (pintype "bidirectional"))
    )
    (net (code "73") (name "unconnected-(U$32-Pad-)") (class "Default")
      (node (ref "U$32") (pin "-") (pinfunction "-_-") (pintype "bidirectional"))
    )
    (net (code "74") (name "unconnected-(U$33-Pad-)") (class "Default")
      (node (ref "U$33") (pin "-") (pinfunction "-_-") (pintype "bidirectional"))
    )
    (net (code "75") (name "unconnected-(U$34-Pad-)") (class "Default")
      (node (ref "U$34") (pin "-") (pinfunction "-_-") (pintype "bidirectional"))
    )
    (net (code "76") (name "unconnected-(U$35-Pad-)") (class "Default")
      (node (ref "U$35") (pin "-") (pinfunction "-_-") (pintype "bidirectional"))
    )
    (net (code "77") (name "unconnected-(U$36-Pad-)") (class "Default")
      (node (ref "U$36") (pin "-") (pinfunction "-_-") (pintype "bidirectional"))
    )
    (net (code "78") (name "unconnected-(U$37-Pad-)") (class "Default")
      (node (ref "U$37") (pin "-") (pinfunction "-_-") (pintype "bidirectional"))
    )
    (net (code "79") (name "unconnected-(U$38-Pad-)") (class "Default")
      (node (ref "U$38") (pin "-") (pinfunction "-_-") (pintype "bidirectional"))
    )
    (net (code "80") (name "unconnected-(U$39-Pad-)") (class "Default")
      (node (ref "U$39") (pin "-") (pinfunction "-_-") (pintype "bidirectional"))
    )
    (net (code "81") (name "unconnected-(U$40-Pad-)") (class "Default")
      (node (ref "U$40") (pin "-") (pinfunction "-_-") (pintype "bidirectional"))
    )
    (net (code "82") (name "unconnected-(U$41-Pad-)") (class "Default")
      (node (ref "U$41") (pin "-") (pinfunction "-_-") (pintype "bidirectional"))
    )
    (net (code "83") (name "unconnected-(U$42-Pad-)") (class "Default")
      (node (ref "U$42") (pin "-") (pinfunction "-_-") (pintype "bidirectional"))
    )
    (net (code "84") (name "unconnected-(U$43-Pad-)") (class "Default")
      (node (ref "U$43") (pin "-") (pinfunction "-_-") (pintype "bidirectional"))
    )
    (net (code "85") (name "unconnected-(U$44-Pad-)") (class "Default")
      (node (ref "U$44") (pin "-") (pinfunction "-_-") (pintype "bidirectional"))
    )
    (net (code "86") (name "unconnected-(U$45-Pad-)") (class "Default")
      (node (ref "U$45") (pin "-") (pinfunction "-_-") (pintype "bidirectional"))
    )
    (net (code "87") (name "unconnected-(U$46-Pad-)") (class "Default")
      (node (ref "U$46") (pin "-") (pinfunction "-_-") (pintype "bidirectional"))
    )
    (net (code "88") (name "unconnected-(U$47-Pad-)") (class "Default")
      (node (ref "U$47") (pin "-") (pinfunction "-_-") (pintype "bidirectional"))
    )
    (net (code "89") (name "unconnected-(U$48-Pad-)") (class "Default")
      (node (ref "U$48") (pin "-") (pinfunction "-_-") (pintype "bidirectional"))
    )
    (net (code "90") (name "unconnected-(U$49-Pad-)") (class "Default")
      (node (ref "U$49") (pin "-") (pinfunction "-_-") (pintype "bidirectional"))
    )
    (net (code "91") (name "unconnected-(U$50-Pad-)") (class "Default")
      (node (ref "U$50") (pin "-") (pinfunction "-_-") (pintype "bidirectional"))
    )
    (net (code "92") (name "unconnected-(U$51-Pad-)") (class "Default")
      (node (ref "U$51") (pin "-") (pinfunction "-_-") (pintype "bidirectional"))
    )
    (net (code "93") (name "unconnected-(U$52-Pad-)") (class "Default")
      (node (ref "U$52") (pin "-") (pinfunction "-_-") (pintype "bidirectional"))
    )
    (net (code "94") (name "unconnected-(U$53-Pad-)") (class "Default")
      (node (ref "U$53") (pin "-") (pinfunction "-_-") (pintype "bidirectional"))
    )
    (net (code "95") (name "unconnected-(U$54-Pad-)") (class "Default")
      (node (ref "U$54") (pin "-") (pinfunction "-_-") (pintype "bidirectional"))
    )
    (net (code "96") (name "unconnected-(U$55-Pad-)") (class "Default")
      (node (ref "U$55") (pin "-") (pinfunction "-_-") (pintype "bidirectional"))
    )
    (net (code "97") (name "unconnected-(U$56-Pad-)") (class "Default")
      (node (ref "U$56") (pin "-") (pinfunction "-_-") (pintype "bidirectional"))
    )
    (net (code "98") (name "unconnected-(U$57-Pad-)") (class "Default")
      (node (ref "U$57") (pin "-") (pinfunction "-_-") (pintype "bidirectional"))
    )
    (net (code "99") (name "unconnected-(U$58-Pad-)") (class "Default")
      (node (ref "U$58") (pin "-") (pinfunction "-_-") (pintype "bidirectional"))
    )
    (net (code "100") (name "unconnected-(U$59-Pad-)") (class "Default")
      (node (ref "U$59") (pin "-") (pinfunction "-_-") (pintype "bidirectional"))
    )
    (net (code "101") (name "unconnected-(U$60-Pad-)") (class "Default")
      (node (ref "U$60") (pin "-") (pinfunction "-_-") (pintype "bidirectional"))
    )
    (net (code "102") (name "unconnected-(U$61-Pad-)") (class "Default")
      (node (ref "U$61") (pin "-") (pinfunction "-_-") (pintype "bidirectional"))
    )
    (net (code "103") (name "unconnected-(U$62-Pad-)") (class "Default")
      (node (ref "U$62") (pin "-") (pinfunction "-_-") (pintype "bidirectional"))
    )
    (net (code "104") (name "unconnected-(U$63-Pad-)") (class "Default")
      (node (ref "U$63") (pin "-") (pinfunction "-_-") (pintype "bidirectional"))
    )
    (net (code "105") (name "unconnected-(U$64-Pad-)") (class "Default")
      (node (ref "U$64") (pin "-") (pinfunction "-_-") (pintype "bidirectional"))
    )
    (net (code "106") (name "unconnected-(U$65-Pad-)") (class "Default")
      (node (ref "U$65") (pin "-") (pinfunction "-_-") (pintype "bidirectional"))
    )
    (net (code "107") (name "unconnected-(U$66-Pad-)") (class "Default")
      (node (ref "U$66") (pin "-") (pinfunction "-_-") (pintype "bidirectional"))
    )
    (net (code "108") (name "unconnected-(U$67-Pad-)") (class "Default")
      (node (ref "U$67") (pin "-") (pinfunction "-_-") (pintype "bidirectional"))
    )
    (net (code "109") (name "unconnected-(U$68-Pad-)") (class "Default")
      (node (ref "U$68") (pin "-") (pinfunction "-_-") (pintype "bidirectional"))
    )
    (net (code "110") (name "unconnected-(U$69-Pad-)") (class "Default")
      (node (ref "U$69") (pin "-") (pinfunction "-_-") (pintype "bidirectional"))
    )
    (net (code "111") (name "unconnected-(U$70-Pad-)") (class "Default")
      (node (ref "U$70") (pin "-") (pinfunction "-_-") (pintype "bidirectional"))
    )
    (net (code "112") (name "unconnected-(U$71-Pad-)") (class "Default")
      (node (ref "U$71") (pin "-") (pinfunction "-_-") (pintype "bidirectional"))
    )
    (net (code "113") (name "unconnected-(U$72-Pad-)") (class "Default")
      (node (ref "U$72") (pin "-") (pinfunction "-_-") (pintype "bidirectional"))
    )
    (net (code "114") (name "unconnected-(U$73-Pad-)") (class "Default")
      (node (ref "U$73") (pin "-") (pinfunction "-_-") (pintype "bidirectional"))
    )
    (net (code "115") (name "unconnected-(U$74-Pad-)") (class "Default")
      (node (ref "U$74") (pin "-") (pinfunction "-_-") (pintype "bidirectional"))
    )
    (net (code "116") (name "unconnected-(U$75-Pad-)") (class "Default")
      (node (ref "U$75") (pin "-") (pinfunction "-_-") (pintype "bidirectional"))
    )
    (net (code "117") (name "unconnected-(U$76-Pad-)") (class "Default")
      (node (ref "U$76") (pin "-") (pinfunction "-_-") (pintype "bidirectional"))
    )
    (net (code "118") (name "unconnected-(U$77-Pad-)") (class "Default")
      (node (ref "U$77") (pin "-") (pinfunction "-_-") (pintype "bidirectional"))
    )
    (net (code "119") (name "unconnected-(U$78-Pad-)") (class "Default")
      (node (ref "U$78") (pin "-") (pinfunction "-_-") (pintype "bidirectional"))
    )
    (net (code "120") (name "unconnected-(U$79-Pad-)") (class "Default")
      (node (ref "U$79") (pin "-") (pinfunction "-_-") (pintype "bidirectional"))
    )
    (net (code "121") (name "unconnected-(U$80-Pad-)") (class "Default")
      (node (ref "U$80") (pin "-") (pinfunction "-_-") (pintype "bidirectional"))
    )
    (net (code "122") (name "unconnected-(U$81-Pad-)") (class "Default")
      (node (ref "U$81") (pin "-") (pinfunction "-_-") (pintype "bidirectional"))
    )
    (net (code "123") (name "unconnected-(U$82-Pad-)") (class "Default")
      (node (ref "U$82") (pin "-") (pinfunction "-_-") (pintype "bidirectional"))
    )
    (net (code "124") (name "unconnected-(U$83-Pad-)") (class "Default")
      (node (ref "U$83") (pin "-") (pinfunction "-_-") (pintype "bidirectional"))
    )
    (net (code "125") (name "unconnected-(U$84-Pad-)") (class "Default")
      (node (ref "U$84") (pin "-") (pinfunction "-_-") (pintype "bidirectional"))
    )
  )
)
